# core.net
KiCad netlist of a schematic drawn in EAGLE
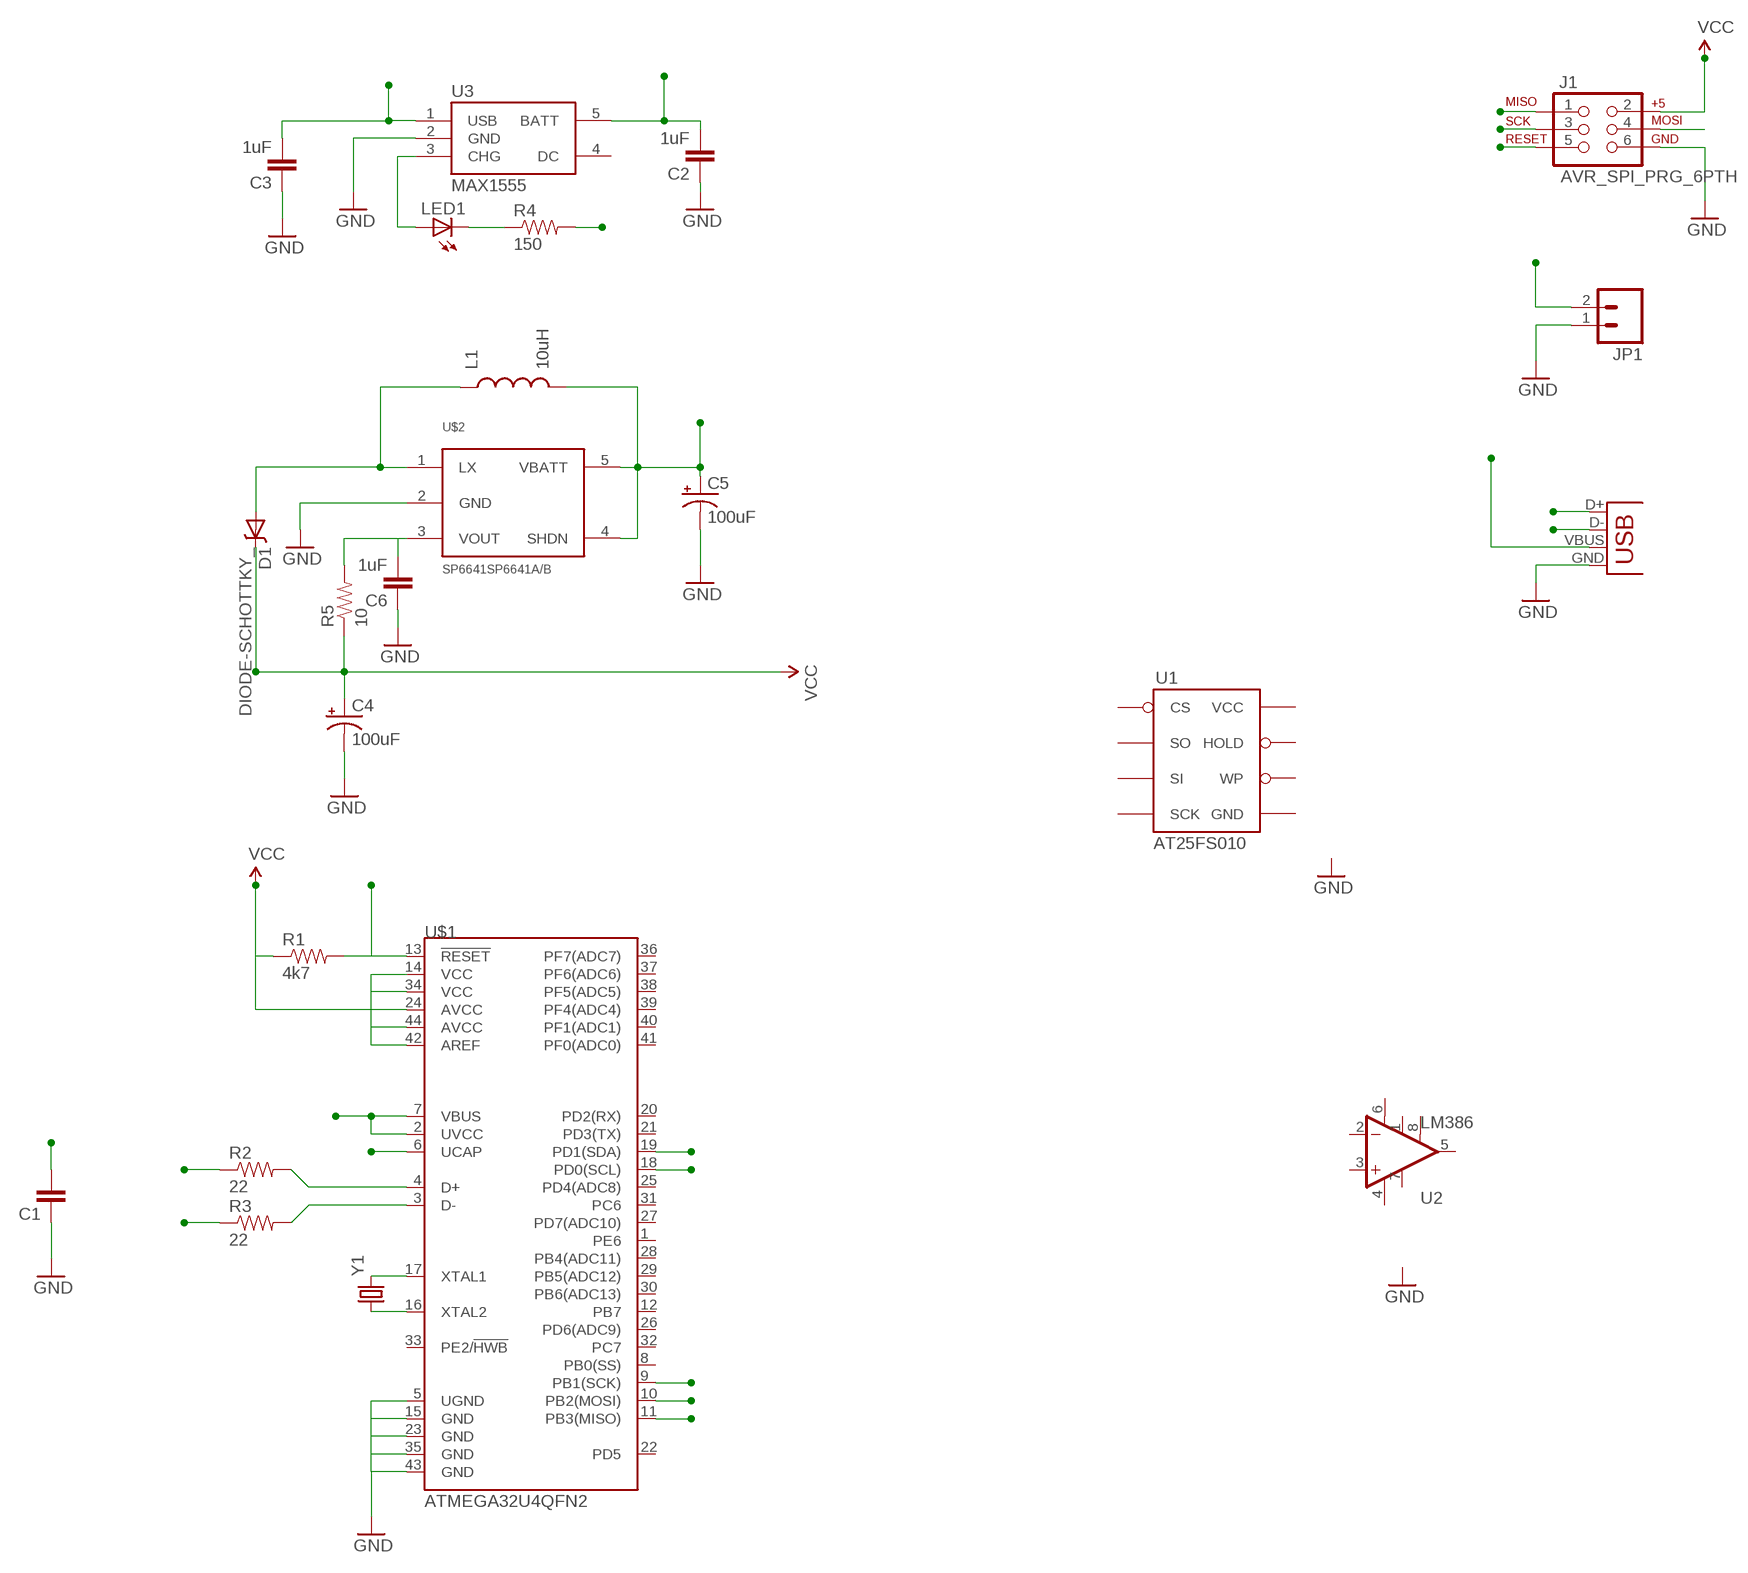
[diagram p0: schematic, sheet 1]

(export (version "E")
  (design (tool "Eeschema 10.0.6"))
  (components
    (comp (ref "C1")
      (value "CAP1206")
      (footprint "eagle-import:1206")
      (libsource (lib "eagle-import") (part "CAP1206"))
    )
    (comp (ref "C2")
      (value "1uF")
      (footprint "eagle-import:1206")
      (libsource (lib "eagle-import") (part "CAP1206"))
    )
    (comp (ref "C3")
      (value "1uF")
      (footprint "eagle-import:1206")
      (libsource (lib "eagle-import") (part "CAP1206"))
    )
    (comp (ref "C4")
      (value "100uF")
      (footprint "eagle-import:PANASONIC_E")
      (libsource (lib "eagle-import") (part "CAP_POLE"))
    )
    (comp (ref "C5")
      (value "100uF")
      (footprint "eagle-import:PANASONIC_E")
      (libsource (lib "eagle-import") (part "CAP_POLE"))
    )
    (comp (ref "C6")
      (value "1uF")
      (footprint "eagle-import:0603-CAP")
      (libsource (lib "eagle-import") (part "CAP0603-CAP"))
    )
    (comp (ref "D1")
      (value "DIODE-SCHOTTKY_")
      (footprint "eagle-import:SMA-DIODE")
      (libsource (lib "eagle-import") (part "DIODE-SCHOTTKY_"))
    )
    (comp (ref "J1")
      (value "AVR_SPI_PRG_6PTH")
      (footprint "eagle-import:2X3")
      (libsource (lib "eagle-import") (part "AVR_SPI_PRG_6PTH"))
    )
    (comp (ref "JP1")
      (value "M02-JST-2MM-SMT")
      (footprint "eagle-import:JST-2-SMD")
      (libsource (lib "eagle-import") (part "M02-JST-2MM-SMT"))
    )
    (comp (ref "L1")
      (value "10uH")
      (footprint "eagle-import:CR75")
      (libsource (lib "eagle-import") (part "INDUCTORCR75"))
    )
    (comp (ref "LED1")
      (value "LED0603")
      (footprint "eagle-import:LED-0603")
      (libsource (lib "eagle-import") (part "LED0603"))
    )
    (comp (ref "R1")
      (value "4k7")
      (footprint "eagle-import:0603-RES")
      (libsource (lib "eagle-import") (part "220-5%"))
    )
    (comp (ref "R2")
      (value "22")
      (footprint "eagle-import:0603-RES")
      (fields (field (name "PROD_ID") "RES-07866"))
      (libsource (lib "eagle-import") (part "220-5%"))
    )
    (comp (ref "R3")
      (value "22")
      (footprint "eagle-import:0603-RES")
      (fields (field (name "PROD_ID") "RES-07866"))
      (libsource (lib "eagle-import") (part "220-5%"))
    )
    (comp (ref "R4")
      (value "150")
      (footprint "eagle-import:0603-RES")
      (fields (field (name "PROD_ID") "RES-07866"))
      (libsource (lib "eagle-import") (part "220-5%"))
    )
    (comp (ref "R5")
      (value "10")
      (footprint "eagle-import:0603-RES")
      (fields (field (name "PROD_ID") "RES-07866"))
      (libsource (lib "eagle-import") (part "220-5%"))
    )
    (comp (ref "U$1")
      (value "ATMEGA32U4QFN2")
      (footprint "eagle-import:QFN-44-NOPAD")
      (libsource (lib "eagle-import") (part "ATMEGA32U4QFN2"))
    )
    (comp (ref "U$2")
      (value "SP6641SP6641A/B")
      (footprint "eagle-import:SOT23-5")
      (libsource (lib "eagle-import") (part "SP6641SP6641A/B"))
    )
    (comp (ref "U1")
      (value "AT25FS010")
      (footprint "eagle-import:SO08WIDE")
      (libsource (lib "eagle-import") (part "AT25FS010"))
    )
    (comp (ref "U2")
      (value "LM386")
      (footprint "eagle-import:DIP08")
      (libsource (lib "eagle-import") (part "LM386"))
    )
    (comp (ref "U3")
      (value "MAX1555")
      (footprint "eagle-import:SOT23-5")
      (libsource (lib "eagle-import") (part "MAX1555"))
    )
    (comp (ref "X1")
      (value "USBSMD")
      (footprint "eagle-import:USB-MINIB")
      (libsource (lib "eagle-import") (part "USBSMD"))
    )
    (comp (ref "Y1")
      (value "CRYSTAL5X3")
      (footprint "eagle-import:CRYSTAL-SMD-5X3")
      (libsource (lib "eagle-import") (part "CRYSTAL5X3"))
    )
  )
  (nets
    (net (code "1") (name "/MISO") (class "Default")
      (node (ref "J1") (pin "1") (pinfunction "1_1") (pintype "passive"))
      (node (ref "U$1") (pin "11") (pinfunction "PB3(MISO)_11") (pintype "bidirectional"))
    )
    (net (code "2") (name "/MOSI") (class "Default")
      (node (ref "J1") (pin "4") (pinfunction "4_4") (pintype "passive"))
      (node (ref "U$1") (pin "10") (pinfunction "PB2(MOSI)_10") (pintype "bidirectional"))
    )
    (net (code "3") (name "/SCK") (class "Default")
      (node (ref "J1") (pin "3") (pinfunction "3_3") (pintype "passive"))
      (node (ref "U$1") (pin "9") (pinfunction "PB1(SCK)_9") (pintype "bidirectional"))
    )
    (net (code "4") (name "/UCAP") (class "Default")
      (node (ref "C1") (pin "2") (pinfunction "2_2") (pintype "passive"))
      (node (ref "U$1") (pin "6") (pinfunction "UCAP_6") (pintype "bidirectional"))
    )
    (net (code "5") (name "/USB_D+") (class "Default")
      (node (ref "R2") (pin "1") (pinfunction "1_1") (pintype "passive"))
      (node (ref "X1") (pin "D+") (pinfunction "D+_D+") (pintype "bidirectional"))
    )
    (net (code "6") (name "/USB_D-") (class "Default")
      (node (ref "R3") (pin "1") (pinfunction "1_1") (pintype "passive"))
      (node (ref "X1") (pin "D-") (pinfunction "D-_D-") (pintype "bidirectional"))
    )
    (net (code "7") (name "/V+") (class "Default")
      (node (ref "U2") (pin "6") (pinfunction "V+_6") (pintype "power_in"))
    )
    (net (code "8") (name "/V-") (class "Default")
      (node (ref "U2") (pin "4") (pinfunction "V-_4") (pintype "power_in"))
    )
    (net (code "9") (name "/VBATT") (class "Default")
      (node (ref "C2") (pin "2") (pinfunction "2_2") (pintype "passive"))
      (node (ref "C5") (pin "+") (pinfunction "+_+") (pintype "passive"))
      (node (ref "JP1") (pin "2") (pinfunction "1_2") (pintype "passive"))
      (node (ref "L1") (pin "P$2") (pinfunction "2_P$2") (pintype "passive"))
      (node (ref "U$2") (pin "4") (pinfunction "SHDN_4") (pintype "bidirectional"))
      (node (ref "U$2") (pin "5") (pinfunction "VBATT_5") (pintype "bidirectional"))
      (node (ref "U3") (pin "5") (pinfunction "BATT_5") (pintype "bidirectional"))
    )
    (net (code "10") (name "/VBUS") (class "Default")
      (node (ref "C3") (pin "2") (pinfunction "2_2") (pintype "passive"))
      (node (ref "R4") (pin "2") (pinfunction "2_2") (pintype "passive"))
      (node (ref "U$1") (pin "2") (pinfunction "UVCC_2") (pintype "bidirectional"))
      (node (ref "U$1") (pin "7") (pinfunction "VBUS_7") (pintype "bidirectional"))
      (node (ref "U3") (pin "1") (pinfunction "USB_1") (pintype "bidirectional"))
      (node (ref "X1") (pin "VBUS") (pinfunction "VBUS_VBUS") (pintype "bidirectional"))
    )
    (net (code "11") (name "/{slash}RESET") (class "Default")
      (node (ref "J1") (pin "5") (pinfunction "5_5") (pintype "passive"))
      (node (ref "R1") (pin "2") (pinfunction "2_2") (pintype "passive"))
      (node (ref "U$1") (pin "13") (pinfunction "~{RESET}_13") (pintype "bidirectional"))
    )
    (net (code "12") (name "GND") (class "Default")
      (node (ref "C1") (pin "1") (pinfunction "1_1") (pintype "passive"))
      (node (ref "C2") (pin "1") (pinfunction "1_1") (pintype "passive"))
      (node (ref "C3") (pin "1") (pinfunction "1_1") (pintype "passive"))
      (node (ref "C4") (pin "-") (pinfunction "-_-") (pintype "passive"))
      (node (ref "C5") (pin "-") (pinfunction "-_-") (pintype "passive"))
      (node (ref "C6") (pin "1") (pinfunction "1_1") (pintype "passive"))
      (node (ref "J1") (pin "6") (pinfunction "6_6") (pintype "passive"))
      (node (ref "JP1") (pin "1") (pinfunction "2_1") (pintype "passive"))
      (node (ref "U$1") (pin "15") (pinfunction "GND_15") (pintype "bidirectional"))
      (node (ref "U$1") (pin "23") (pinfunction "GND_23") (pintype "bidirectional"))
      (node (ref "U$1") (pin "35") (pinfunction "GND_35") (pintype "bidirectional"))
      (node (ref "U$1") (pin "43") (pinfunction "GND_43") (pintype "bidirectional"))
      (node (ref "U$1") (pin "5") (pinfunction "UGND_5") (pintype "bidirectional"))
      (node (ref "U$2") (pin "2") (pinfunction "GND_2") (pintype "bidirectional"))
      (node (ref "U3") (pin "2") (pinfunction "GND_2") (pintype "bidirectional"))
      (node (ref "X1") (pin "GND") (pinfunction "GND_GND") (pintype "bidirectional"))
    )
    (net (code "13") (name "Net-(L1-1)") (class "Default")
      (node (ref "D1") (pin "A") (pinfunction "A_A") (pintype "passive"))
      (node (ref "L1") (pin "P$1") (pinfunction "1_P$1") (pintype "passive"))
      (node (ref "U$2") (pin "1") (pinfunction "LX_1") (pintype "bidirectional"))
    )
    (net (code "14") (name "Net-(LED1-PadC)") (class "Default")
      (node (ref "LED1") (pin "C") (pinfunction "C_C") (pintype "passive"))
      (node (ref "R4") (pin "1") (pinfunction "1_1") (pintype "passive"))
    )
    (net (code "15") (name "Net-(U$1-D+)") (class "Default")
      (node (ref "R2") (pin "2") (pinfunction "2_2") (pintype "passive"))
      (node (ref "U$1") (pin "4") (pinfunction "D+_4") (pintype "bidirectional"))
    )
    (net (code "16") (name "Net-(U$1-D-)") (class "Default")
      (node (ref "R3") (pin "2") (pinfunction "2_2") (pintype "passive"))
      (node (ref "U$1") (pin "3") (pinfunction "D-_3") (pintype "bidirectional"))
    )
    (net (code "17") (name "Net-(U$1-XTAL1)") (class "Default")
      (node (ref "U$1") (pin "17") (pinfunction "XTAL1_17") (pintype "bidirectional"))
      (node (ref "Y1") (pin "3") (pinfunction "2_3") (pintype "passive"))
    )
    (net (code "18") (name "Net-(U$1-XTAL2)") (class "Default")
      (node (ref "U$1") (pin "16") (pinfunction "XTAL2_16") (pintype "bidirectional"))
      (node (ref "Y1") (pin "1") (pinfunction "1_1") (pintype "passive"))
    )
    (net (code "19") (name "Net-(U$2-VOUT)") (class "Default")
      (node (ref "C6") (pin "2") (pinfunction "2_2") (pintype "passive"))
      (node (ref "R5") (pin "2") (pinfunction "2_2") (pintype "passive"))
      (node (ref "U$2") (pin "3") (pinfunction "VOUT_3") (pintype "bidirectional"))
    )
    (net (code "20") (name "Net-(U3-CHG)") (class "Default")
      (node (ref "LED1") (pin "A") (pinfunction "A_A") (pintype "passive"))
      (node (ref "U3") (pin "3") (pinfunction "CHG_3") (pintype "bidirectional"))
    )
    (net (code "21") (name "VCC") (class "Default")
      (node (ref "C4") (pin "+") (pinfunction "+_+") (pintype "passive"))
      (node (ref "D1") (pin "C") (pinfunction "C_C") (pintype "passive"))
      (node (ref "J1") (pin "2") (pinfunction "2_2") (pintype "passive"))
      (node (ref "R1") (pin "1") (pinfunction "1_1") (pintype "passive"))
      (node (ref "R5") (pin "1") (pinfunction "1_1") (pintype "passive"))
      (node (ref "U$1") (pin "14") (pinfunction "VCC_14") (pintype "bidirectional"))
      (node (ref "U$1") (pin "24") (pinfunction "AVCC_24") (pintype "bidirectional"))
      (node (ref "U$1") (pin "34") (pinfunction "VCC_34") (pintype "bidirectional"))
      (node (ref "U$1") (pin "42") (pinfunction "AREF_42") (pintype "bidirectional"))
      (node (ref "U$1") (pin "44") (pinfunction "AVCC_44") (pintype "bidirectional"))
    )
    (net (code "22") (name "unconnected-(U$1-PB0(SS)-Pad8)") (class "Default")
      (node (ref "U$1") (pin "8") (pinfunction "PB0(SS)_8") (pintype "bidirectional"))
    )
    (net (code "23") (name "unconnected-(U$1-PB4(ADC11)-Pad28)") (class "Default")
      (node (ref "U$1") (pin "28") (pinfunction "PB4(ADC11)_28") (pintype "bidirectional"))
    )
    (net (code "24") (name "unconnected-(U$1-PB5(ADC12)-Pad29)") (class "Default")
      (node (ref "U$1") (pin "29") (pinfunction "PB5(ADC12)_29") (pintype "bidirectional"))
    )
    (net (code "25") (name "unconnected-(U$1-PB6(ADC13)-Pad30)") (class "Default")
      (node (ref "U$1") (pin "30") (pinfunction "PB6(ADC13)_30") (pintype "bidirectional"))
    )
    (net (code "26") (name "unconnected-(U$1-PB7-Pad12)") (class "Default")
      (node (ref "U$1") (pin "12") (pinfunction "PB7_12") (pintype "bidirectional"))
    )
    (net (code "27") (name "unconnected-(U$1-PC6-Pad31)") (class "Default")
      (node (ref "U$1") (pin "31") (pinfunction "PC6_31") (pintype "bidirectional"))
    )
    (net (code "28") (name "unconnected-(U$1-PC7-Pad32)") (class "Default")
      (node (ref "U$1") (pin "32") (pinfunction "PC7_32") (pintype "bidirectional"))
    )
    (net (code "29") (name "unconnected-(U$1-PD0(SCL)-Pad18)") (class "Default")
      (node (ref "U$1") (pin "18") (pinfunction "PD0(SCL)_18") (pintype "bidirectional"))
    )
    (net (code "30") (name "unconnected-(U$1-PD1(SDA)-Pad19)") (class "Default")
      (node (ref "U$1") (pin "19") (pinfunction "PD1(SDA)_19") (pintype "bidirectional"))
    )
    (net (code "31") (name "unconnected-(U$1-PD2(RX)-Pad20)") (class "Default")
      (node (ref "U$1") (pin "20") (pinfunction "PD2(RX)_20") (pintype "bidirectional"))
    )
    (net (code "32") (name "unconnected-(U$1-PD3(TX)-Pad21)") (class "Default")
      (node (ref "U$1") (pin "21") (pinfunction "PD3(TX)_21") (pintype "bidirectional"))
    )
    (net (code "33") (name "unconnected-(U$1-PD4(ADC8)-Pad25)") (class "Default")
      (node (ref "U$1") (pin "25") (pinfunction "PD4(ADC8)_25") (pintype "bidirectional"))
    )
    (net (code "34") (name "unconnected-(U$1-PD5-Pad22)") (class "Default")
      (node (ref "U$1") (pin "22") (pinfunction "PD5_22") (pintype "bidirectional"))
    )
    (net (code "35") (name "unconnected-(U$1-PD6(ADC9)-Pad26)") (class "Default")
      (node (ref "U$1") (pin "26") (pinfunction "PD6(ADC9)_26") (pintype "bidirectional"))
    )
    (net (code "36") (name "unconnected-(U$1-PD7(ADC10)-Pad27)") (class "Default")
      (node (ref "U$1") (pin "27") (pinfunction "PD7(ADC10)_27") (pintype "bidirectional"))
    )
    (net (code "37") (name "unconnected-(U$1-PE2{slash}~{HWB}-Pad33)") (class "Default")
      (node (ref "U$1") (pin "33") (pinfunction "PE2/~{HWB}_33") (pintype "bidirectional"))
    )
    (net (code "38") (name "unconnected-(U$1-PE6-Pad1)") (class "Default")
      (node (ref "U$1") (pin "1") (pinfunction "PE6_1") (pintype "bidirectional"))
    )
    (net (code "39") (name "unconnected-(U$1-PF0(ADC0)-Pad41)") (class "Default")
      (node (ref "U$1") (pin "41") (pinfunction "PF0(ADC0)_41") (pintype "bidirectional"))
    )
    (net (code "40") (name "unconnected-(U$1-PF1(ADC1)-Pad40)") (class "Default")
      (node (ref "U$1") (pin "40") (pinfunction "PF1(ADC1)_40") (pintype "bidirectional"))
    )
    (net (code "41") (name "unconnected-(U$1-PF4(ADC4)-Pad39)") (class "Default")
      (node (ref "U$1") (pin "39") (pinfunction "PF4(ADC4)_39") (pintype "bidirectional"))
    )
    (net (code "42") (name "unconnected-(U$1-PF5(ADC5)-Pad38)") (class "Default")
      (node (ref "U$1") (pin "38") (pinfunction "PF5(ADC5)_38") (pintype "bidirectional"))
    )
    (net (code "43") (name "unconnected-(U$1-PF6(ADC6)-Pad37)") (class "Default")
      (node (ref "U$1") (pin "37") (pinfunction "PF6(ADC6)_37") (pintype "bidirectional"))
    )
    (net (code "44") (name "unconnected-(U$1-PF7(ADC7)-Pad36)") (class "Default")
      (node (ref "U$1") (pin "36") (pinfunction "PF7(ADC7)_36") (pintype "bidirectional"))
    )
    (net (code "45") (name "unconnected-(U1-CS-Pad1)") (class "Default")
      (node (ref "U1") (pin "1") (pinfunction "CS_1") (pintype "bidirectional"))
    )
    (net (code "46") (name "unconnected-(U1-GND-Pad4)") (class "Default")
      (node (ref "U1") (pin "4") (pinfunction "GND_4") (pintype "bidirectional"))
    )
    (net (code "47") (name "unconnected-(U1-HOLD-Pad7)") (class "Default")
      (node (ref "U1") (pin "7") (pinfunction "HOLD_7") (pintype "bidirectional"))
    )
    (net (code "48") (name "unconnected-(U1-SCK-Pad6)") (class "Default")
      (node (ref "U1") (pin "6") (pinfunction "SCK_6") (pintype "bidirectional"))
    )
    (net (code "49") (name "unconnected-(U1-SI-Pad5)") (class "Default")
      (node (ref "U1") (pin "5") (pinfunction "SI_5") (pintype "bidirectional"))
    )
    (net (code "50") (name "unconnected-(U1-SO-Pad2)") (class "Default")
      (node (ref "U1") (pin "2") (pinfunction "SO_2") (pintype "bidirectional"))
    )
    (net (code "51") (name "unconnected-(U1-VCC-Pad8)") (class "Default")
      (node (ref "U1") (pin "8") (pinfunction "VCC_8") (pintype "bidirectional"))
    )
    (net (code "52") (name "unconnected-(U1-WP-Pad3)") (class "Default")
      (node (ref "U1") (pin "3") (pinfunction "WP_3") (pintype "bidirectional"))
    )
    (net (code "53") (name "unconnected-(U2-+IN-Pad3)") (class "Default")
      (node (ref "U2") (pin "3") (pinfunction "+IN_3") (pintype "input"))
    )
    (net (code "54") (name "unconnected-(U2--IN-Pad2)") (class "Default")
      (node (ref "U2") (pin "2") (pinfunction "-IN_2") (pintype "input"))
    )
    (net (code "55") (name "unconnected-(U2-BP-Pad7)") (class "Default")
      (node (ref "U2") (pin "7") (pinfunction "BP_7") (pintype "bidirectional"))
    )
    (net (code "56") (name "unconnected-(U2-GAIN-Pad1)") (class "Default")
      (node (ref "U2") (pin "1") (pinfunction "GAIN_1") (pintype "bidirectional"))
    )
    (net (code "57") (name "unconnected-(U2-GAIN-Pad8)") (class "Default")
      (node (ref "U2") (pin "8") (pinfunction "GAIN_8") (pintype "bidirectional"))
    )
    (net (code "58") (name "unconnected-(U2-OUT-Pad5)") (class "Default")
      (node (ref "U2") (pin "5") (pinfunction "OUT_5") (pintype "output"))
    )
    (net (code "59") (name "unconnected-(U3-DC-Pad4)") (class "Default")
      (node (ref "U3") (pin "4") (pinfunction "DC_4") (pintype "bidirectional"))
    )
  )
)
